# chipchestra-v05-actuators.net
KiCad netlist of a schematic drawn in EAGLE
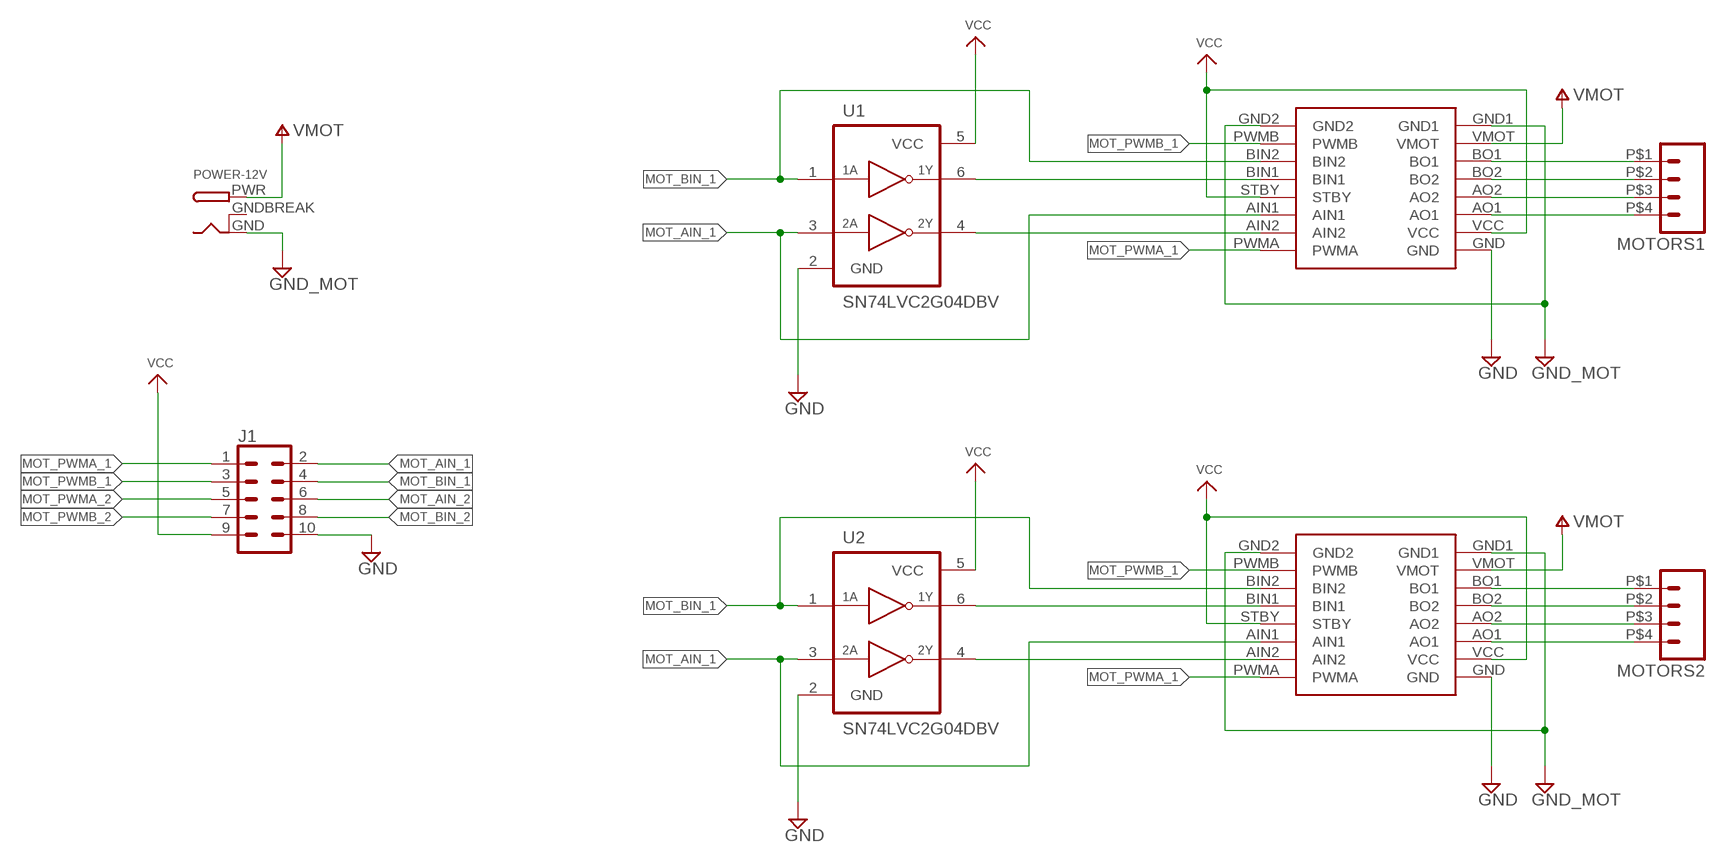
[diagram p0: schematic, sheet 1]

(export (version "E")
  (design (tool "Eeschema 10.0.6"))
  (components
    (comp (ref "J1")
      (value "CONN_05X2SHD_LOCK")
      (footprint "eagle-import:2X5-SHROUDED_LOCK")
      (libsource (lib "eagle-import") (part "CONN_05X2SHD_LOCK"))
    )
    (comp (ref "MOTORS1")
      (value "M04")
      (footprint "eagle-import:SPRINGTERMINAL-2.54MM-4")
      (libsource (lib "eagle-import") (part "M04"))
    )
    (comp (ref "MOTORS2")
      (value "M04")
      (footprint "eagle-import:SPRINGTERMINAL-2.54MM-4")
      (libsource (lib "eagle-import") (part "M04"))
    )
    (comp (ref "POWER-12V")
      (value "DCBARRELPTH")
      (footprint "eagle-import:DCJACK_2MM_PTH")
      (libsource (lib "eagle-import") (part "DCBARRELPTH"))
    )
    (comp (ref "U$1")
      (value "POLOLU_TB6612FNG")
      (footprint "eagle-import:POLOLU_TB6612FNG")
      (libsource (lib "eagle-import") (part "POLOLU_TB6612FNG"))
    )
    (comp (ref "U$7")
      (value "POLOLU_TB6612FNG")
      (footprint "eagle-import:POLOLU_TB6612FNG")
      (libsource (lib "eagle-import") (part "POLOLU_TB6612FNG"))
    )
    (comp (ref "U1")
      (value "SN74LVC2G04DBV")
      (footprint "eagle-import:SOT23-6")
      (libsource (lib "eagle-import") (part "SN74LVC2G04DBV"))
    )
    (comp (ref "U2")
      (value "SN74LVC2G04DBV")
      (footprint "eagle-import:SOT23-6")
      (libsource (lib "eagle-import") (part "SN74LVC2G04DBV"))
    )
  )
  (nets
    (net (code "1") (name "/GNDBREAK") (class "Default")
      (node (ref "POWER-12V") (pin "GNDBREAK") (pinfunction "GNDBREAK_GNDBREAK") (pintype "power_in"))
    )
    (net (code "2") (name "GND") (class "Default")
      (node (ref "J1") (pin "10") (pinfunction "10_10") (pintype "passive"))
      (node (ref "U$1") (pin "GND") (pinfunction "GND_GND") (pintype "bidirectional"))
      (node (ref "U$7") (pin "GND") (pinfunction "GND_GND") (pintype "bidirectional"))
      (node (ref "U1") (pin "2") (pinfunction "GND_2") (pintype "power_in"))
      (node (ref "U2") (pin "2") (pinfunction "GND_2") (pintype "power_in"))
    )
    (net (code "3") (name "GND_MOT") (class "Default")
      (node (ref "POWER-12V") (pin "GND") (pinfunction "GND_GND") (pintype "power_in"))
      (node (ref "U$1") (pin "GND1") (pinfunction "GND1_GND1") (pintype "bidirectional"))
      (node (ref "U$1") (pin "GND2") (pinfunction "GND2_GND2") (pintype "bidirectional"))
      (node (ref "U$7") (pin "GND1") (pinfunction "GND1_GND1") (pintype "bidirectional"))
      (node (ref "U$7") (pin "GND2") (pinfunction "GND2_GND2") (pintype "bidirectional"))
    )
    (net (code "4") (name "MOT_AIN_1") (class "Default")
      (node (ref "J1") (pin "2") (pinfunction "2_2") (pintype "passive"))
      (node (ref "U$1") (pin "AIN1") (pinfunction "AIN1_AIN1") (pintype "bidirectional"))
      (node (ref "U$7") (pin "AIN1") (pinfunction "AIN1_AIN1") (pintype "bidirectional"))
      (node (ref "U1") (pin "3") (pinfunction "2A_3") (pintype "input"))
      (node (ref "U2") (pin "3") (pinfunction "2A_3") (pintype "input"))
    )
    (net (code "5") (name "MOT_AIN_2") (class "Default")
      (node (ref "J1") (pin "6") (pinfunction "6_6") (pintype "passive"))
    )
    (net (code "6") (name "MOT_BIN_1") (class "Default")
      (node (ref "J1") (pin "4") (pinfunction "4_4") (pintype "passive"))
      (node (ref "U$1") (pin "BIN2") (pinfunction "BIN2_BIN2") (pintype "bidirectional"))
      (node (ref "U$7") (pin "BIN2") (pinfunction "BIN2_BIN2") (pintype "bidirectional"))
      (node (ref "U1") (pin "1") (pinfunction "1A_1") (pintype "input"))
      (node (ref "U2") (pin "1") (pinfunction "1A_1") (pintype "input"))
    )
    (net (code "7") (name "MOT_BIN_2") (class "Default")
      (node (ref "J1") (pin "8") (pinfunction "8_8") (pintype "passive"))
    )
    (net (code "8") (name "MOT_PWMA_1") (class "Default")
      (node (ref "J1") (pin "1") (pinfunction "1_1") (pintype "passive"))
      (node (ref "U$1") (pin "PWMA") (pinfunction "PWMA_PWMA") (pintype "bidirectional"))
      (node (ref "U$7") (pin "PWMA") (pinfunction "PWMA_PWMA") (pintype "bidirectional"))
    )
    (net (code "9") (name "MOT_PWMA_2") (class "Default")
      (node (ref "J1") (pin "5") (pinfunction "5_5") (pintype "passive"))
    )
    (net (code "10") (name "MOT_PWMB_1") (class "Default")
      (node (ref "J1") (pin "3") (pinfunction "3_3") (pintype "passive"))
      (node (ref "U$1") (pin "PWMB") (pinfunction "PWMB_PWMB") (pintype "bidirectional"))
      (node (ref "U$7") (pin "PWMB") (pinfunction "PWMB_PWMB") (pintype "bidirectional"))
    )
    (net (code "11") (name "MOT_PWMB_2") (class "Default")
      (node (ref "J1") (pin "7") (pinfunction "7_7") (pintype "passive"))
    )
    (net (code "12") (name "Net-(MOTORS1-1)") (class "Default")
      (node (ref "MOTORS1") (pin "P$1") (pinfunction "1_P$1") (pintype "passive"))
      (node (ref "U$7") (pin "BO1") (pinfunction "BO1_BO1") (pintype "bidirectional"))
    )
    (net (code "13") (name "Net-(MOTORS1-2)") (class "Default")
      (node (ref "MOTORS1") (pin "P$2") (pinfunction "2_P$2") (pintype "passive"))
      (node (ref "U$7") (pin "BO2") (pinfunction "BO2_BO2") (pintype "bidirectional"))
    )
    (net (code "14") (name "Net-(MOTORS1-3)") (class "Default")
      (node (ref "MOTORS1") (pin "P$3") (pinfunction "3_P$3") (pintype "passive"))
      (node (ref "U$7") (pin "AO2") (pinfunction "AO2_AO2") (pintype "bidirectional"))
    )
    (net (code "15") (name "Net-(MOTORS1-4)") (class "Default")
      (node (ref "MOTORS1") (pin "P$4") (pinfunction "4_P$4") (pintype "passive"))
      (node (ref "U$7") (pin "AO1") (pinfunction "AO1_AO1") (pintype "bidirectional"))
    )
    (net (code "16") (name "Net-(MOTORS2-1)") (class "Default")
      (node (ref "MOTORS2") (pin "P$1") (pinfunction "1_P$1") (pintype "passive"))
      (node (ref "U$1") (pin "BO1") (pinfunction "BO1_BO1") (pintype "bidirectional"))
    )
    (net (code "17") (name "Net-(MOTORS2-2)") (class "Default")
      (node (ref "MOTORS2") (pin "P$2") (pinfunction "2_P$2") (pintype "passive"))
      (node (ref "U$1") (pin "BO2") (pinfunction "BO2_BO2") (pintype "bidirectional"))
    )
    (net (code "18") (name "Net-(MOTORS2-3)") (class "Default")
      (node (ref "MOTORS2") (pin "P$3") (pinfunction "3_P$3") (pintype "passive"))
      (node (ref "U$1") (pin "AO2") (pinfunction "AO2_AO2") (pintype "bidirectional"))
    )
    (net (code "19") (name "Net-(MOTORS2-4)") (class "Default")
      (node (ref "MOTORS2") (pin "P$4") (pinfunction "4_P$4") (pintype "passive"))
      (node (ref "U$1") (pin "AO1") (pinfunction "AO1_AO1") (pintype "bidirectional"))
    )
    (net (code "20") (name "Net-(U1-1Y)") (class "Default")
      (node (ref "U$7") (pin "BIN1") (pinfunction "BIN1_BIN1") (pintype "bidirectional"))
      (node (ref "U1") (pin "6") (pinfunction "1Y_6") (pintype "output"))
    )
    (net (code "21") (name "Net-(U1-2Y)") (class "Default")
      (node (ref "U$7") (pin "AIN2") (pinfunction "AIN2_AIN2") (pintype "bidirectional"))
      (node (ref "U1") (pin "4") (pinfunction "2Y_4") (pintype "output"))
    )
    (net (code "22") (name "Net-(U2-1Y)") (class "Default")
      (node (ref "U$1") (pin "BIN1") (pinfunction "BIN1_BIN1") (pintype "bidirectional"))
      (node (ref "U2") (pin "6") (pinfunction "1Y_6") (pintype "output"))
    )
    (net (code "23") (name "Net-(U2-2Y)") (class "Default")
      (node (ref "U$1") (pin "AIN2") (pinfunction "AIN2_AIN2") (pintype "bidirectional"))
      (node (ref "U2") (pin "4") (pinfunction "2Y_4") (pintype "output"))
    )
    (net (code "24") (name "V+") (class "Default")
      (node (ref "POWER-12V") (pin "PWR") (pinfunction "PWR_PWR") (pintype "power_in"))
      (node (ref "U$1") (pin "VMOT") (pinfunction "VMOT_VMOT") (pintype "bidirectional"))
      (node (ref "U$7") (pin "VMOT") (pinfunction "VMOT_VMOT") (pintype "bidirectional"))
    )
    (net (code "25") (name "VCC") (class "Default")
      (node (ref "J1") (pin "9") (pinfunction "9_9") (pintype "passive"))
      (node (ref "U$1") (pin "STBY") (pinfunction "STBY_STBY") (pintype "bidirectional"))
      (node (ref "U$1") (pin "VCC") (pinfunction "VCC_VCC") (pintype "bidirectional"))
      (node (ref "U$7") (pin "STBY") (pinfunction "STBY_STBY") (pintype "bidirectional"))
      (node (ref "U$7") (pin "VCC") (pinfunction "VCC_VCC") (pintype "bidirectional"))
      (node (ref "U1") (pin "5") (pinfunction "VCC_5") (pintype "power_in"))
      (node (ref "U2") (pin "5") (pinfunction "VCC_5") (pintype "power_in"))
    )
  )
)
